# Sheet1.net
KiCad netlist of a schematic drawn in Altium Designer
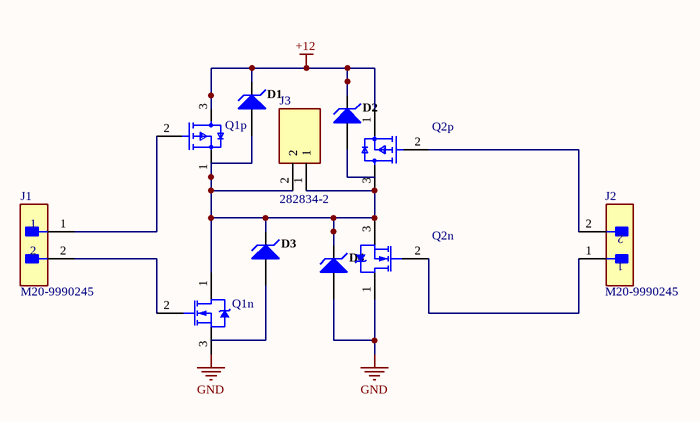
[diagram p0: Sheet1.SchDoc]

(export (version "E")
  (design (tool "Eeschema 10.0.6"))
  (components
    (comp (ref "D1")
      (value "1N4732A")
      (footprint "FAIR-DO-41-2_V")
      (description "Zener Diode, 4.7V, 1W, 5%, -65 to 200 degC, 2-Pin DO-41, Body 2.72 x 5.2 mm, RoHS")
      (fields (field (name "TOLERANCE") "5%") (field (name "MANUFACTURER") "Fairchild Semiconductor"))
      (libsource (lib "Altium Content Vault") (part "FAIR-DZEN-A1K2-2"))
    )
    (comp (ref "D2")
      (value "1N4732A")
      (footprint "FAIR-DO-41-2_V")
      (description "Zener Diode, 4.7V, 1W, 5%, -65 to 200 degC, 2-Pin DO-41, Body 2.72 x 5.2 mm, RoHS")
      (fields (field (name "TOLERANCE") "5%") (field (name "MANUFACTURER") "Fairchild Semiconductor"))
      (libsource (lib "Altium Content Vault") (part "FAIR-DZEN-A1K2-2"))
    )
    (comp (ref "D3")
      (value "1N4732A")
      (footprint "FAIR-DO-41-2_V")
      (description "Zener Diode, 4.7V, 1W, 5%, -65 to 200 degC, 2-Pin DO-41, Body 2.72 x 5.2 mm, RoHS")
      (fields (field (name "TOLERANCE") "5%") (field (name "MANUFACTURER") "Fairchild Semiconductor"))
      (libsource (lib "Altium Content Vault") (part "FAIR-DZEN-A1K2-2"))
    )
    (comp (ref "D4")
      (value "1N4732A")
      (footprint "FAIR-DO-41-2_V")
      (description "Zener Diode, 4.7V, 1W, 5%, -65 to 200 degC, 2-Pin DO-41, Body 2.72 x 5.2 mm, RoHS")
      (fields (field (name "TOLERANCE") "5%") (field (name "MANUFACTURER") "Fairchild Semiconductor"))
      (libsource (lib "Altium Content Vault") (part "FAIR-DZEN-A1K2-2"))
    )
    (comp (ref "J1")
      (value "M20-9990245")
      (footprint "FP-M20-9990245-MFG")
      (description "CONN HEADER VERT 2POS 2.54MM")
      (fields (field (name "VOLTAGE") "50V"))
      (libsource (lib "Altium Content Vault") (part "3bc925449376181038e59eaffc5286c"))
    )
    (comp (ref "J2")
      (value "M20-9990245")
      (footprint "FP-M20-9990245-MFG")
      (description "CONN HEADER VERT 2POS 2.54MM")
      (fields (field (name "VOLTAGE") "50V"))
      (libsource (lib "") (part "3bc925449376181038e59eaffc5286c_1"))
    )
    (comp (ref "J3")
      (value "282834-2")
      (footprint "TE_282834-2")
      (fields (field (name "MF") "{'manufacturer': u'TE Connectivity'}"))
      (libsource (lib "282834-2") (part "282834-2"))
    )
    (comp (ref "Q1n")
      (value "BS170")
      (footprint "ONSC-TO-92-3-29-11")
      (description "Small Signal MOSFET, 500 mA, 60 V, N-Channel, 3-Pin TO-92, Bulk Box")
      (fields (field (name "MANUFACTURER") "On Semiconductor"))
      (libsource (lib "Altium Content Vault") (part "ONSC-NMOS-D1G2S3-3"))
    )
    (comp (ref "Q1p")
      (value "VP2450N3-G")
      (footprint "FP-N3-MFG")
      (description "VP2450N3-G Transistor MOSFET P-CH 500V 0.1A 3-Pin TO-92")
      (libsource (lib "Altium Content Vault") (part "275f369e5121f43e2d59673836ee453"))
    )
    (comp (ref "Q2n")
      (value "BS170")
      (footprint "ONSC-TO-92-3-29-11")
      (description "Small Signal MOSFET, 500 mA, 60 V, N-Channel, 3-Pin TO-92, Bulk Box")
      (fields (field (name "MANUFACTURER") "On Semiconductor"))
      (libsource (lib "Altium Content Vault") (part "ONSC-NMOS-D1G2S3-3"))
    )
    (comp (ref "Q2p")
      (value "VP2450N3-G")
      (footprint "FP-N3-MFG")
      (description "VP2450N3-G Transistor MOSFET P-CH 500V 0.1A 3-Pin TO-92")
      (libsource (lib "Altium Content Vault") (part "275f369e5121f43e2d59673836ee453"))
    )
  )
  (nets
    (net (code "1") (name "+12") (class "Default")
      (node (ref "D1") (pin "2") (pinfunction "K_2") (pintype "passive"))
      (node (ref "D2") (pin "2") (pinfunction "K_2") (pintype "passive"))
      (node (ref "Q1p") (pin "3") (pinfunction "DRAIN_3") (pintype "passive"))
      (node (ref "Q2p") (pin "1") (pinfunction "SOURCE_1") (pintype "passive"))
    )
    (net (code "2") (name "GND") (class "Default")
      (node (ref "D4") (pin "1") (pinfunction "A_1") (pintype "passive"))
      (node (ref "Q1n") (pin "3") (pinfunction "S_3") (pintype "passive"))
      (node (ref "Q2n") (pin "1") (pinfunction "D_1") (pintype "passive"))
    )
    (net (code "3") (name "Net-(D1-A)") (class "Default")
      (node (ref "D1") (pin "1") (pinfunction "A_1") (pintype "passive"))
      (node (ref "D3") (pin "2") (pinfunction "K_2") (pintype "passive"))
      (node (ref "D4") (pin "2") (pinfunction "K_2") (pintype "passive"))
      (node (ref "J3") (pin "1") (pinfunction "1_1") (pintype "passive"))
      (node (ref "J3") (pin "2") (pinfunction "2_2") (pintype "passive"))
      (node (ref "Q1n") (pin "1") (pinfunction "D_1") (pintype "passive"))
      (node (ref "Q1p") (pin "1") (pinfunction "SOURCE_1") (pintype "passive"))
      (node (ref "Q2n") (pin "3") (pinfunction "S_3") (pintype "passive"))
      (node (ref "Q2p") (pin "3") (pinfunction "DRAIN_3") (pintype "passive"))
    )
    (net (code "4") (name "Net-(Q1n-G)") (class "Default")
      (node (ref "J1") (pin "2") (pinfunction "2_2") (pintype "passive"))
      (node (ref "Q1n") (pin "2") (pinfunction "G_2") (pintype "passive"))
    )
    (net (code "5") (name "Net-(Q1p-GATE)") (class "Default")
      (node (ref "J1") (pin "1") (pinfunction "1_1") (pintype "passive"))
      (node (ref "Q1p") (pin "2") (pinfunction "GATE_2") (pintype "passive"))
    )
    (net (code "6") (name "Net-(Q2n-G)") (class "Default")
      (node (ref "J2") (pin "1") (pinfunction "1_1") (pintype "passive"))
      (node (ref "Q2n") (pin "2") (pinfunction "G_2") (pintype "passive"))
    )
    (net (code "7") (name "Net-(Q2p-GATE)") (class "Default")
      (node (ref "J2") (pin "2") (pinfunction "2_2") (pintype "passive"))
      (node (ref "Q2p") (pin "2") (pinfunction "GATE_2") (pintype "passive"))
    )
    (net (code "8") (name "unconnected-(D2-A-Pad1)") (class "Default")
      (node (ref "D2") (pin "1") (pinfunction "A_1") (pintype "passive"))
    )
    (net (code "9") (name "unconnected-(D3-A-Pad1)") (class "Default")
      (node (ref "D3") (pin "1") (pinfunction "A_1") (pintype "passive"))
    )
  )
)
